# 06_eMMC.net
KiCad netlist of a schematic drawn in Altium Designer
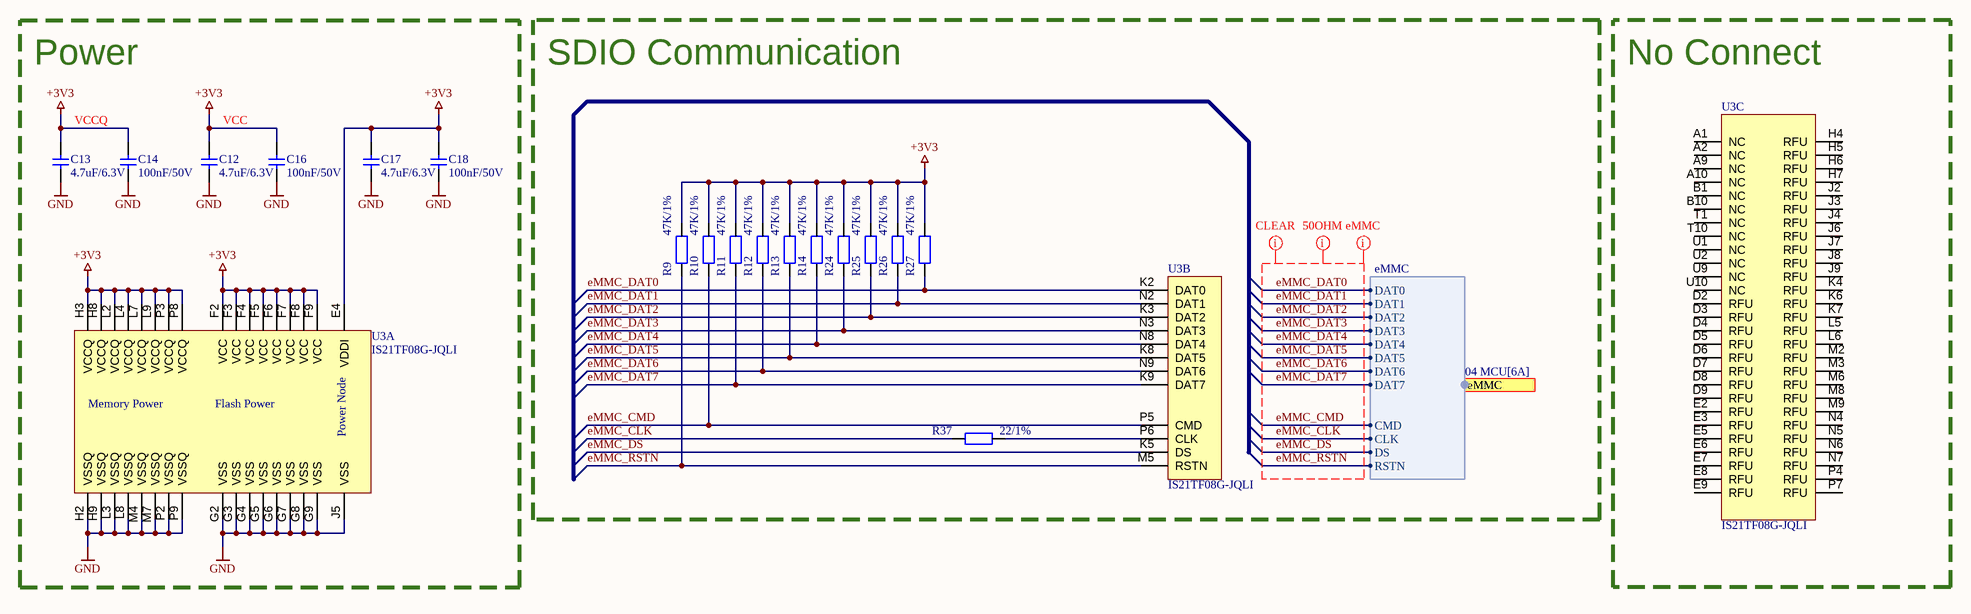
[diagram p0: 06 eMMC.SchDoc]

(export (version "E")
  (design (tool "Eeschema 10.0.6"))
  (components
    (comp (ref "C12")
      (value "4.7uF/6.3V")
      (footprint "CAPC1005X06M-0402")
      (description "4.7 µF ±20% 6.3V Ceramic Capacitor X5R 0402 (1005 Metric)")
      (fields (field (name "MPN") "GRM155R60J475ME47D"))
      (libsource (lib "Symbol") (part "GRM155R60J475ME47D"))
    )
    (comp (ref "C13")
      (value "4.7uF/6.3V")
      (footprint "CAPC1005X06M-0402")
      (description "4.7 µF ±20% 6.3V Ceramic Capacitor X5R 0402 (1005 Metric)")
      (fields (field (name "MPN") "GRM155R60J475ME47D"))
      (libsource (lib "Symbol") (part "GRM155R60J475ME47D"))
    )
    (comp (ref "C14")
      (value "100nF/50V")
      (footprint "CAPC1005X06M-0402")
      (description "0.1 µF ±10% 50V Ceramic Capacitor X7R 0402 (1005 Metric)")
      (fields (field (name "MPN") "GRM155R71H104KE14D"))
      (libsource (lib "Symbol") (part "GRM155R71H104KE14D"))
    )
    (comp (ref "C16")
      (value "100nF/50V")
      (footprint "CAPC1005X06M-0402")
      (description "0.1 µF ±10% 50V Ceramic Capacitor X7R 0402 (1005 Metric)")
      (fields (field (name "MPN") "GRM155R71H104KE14D"))
      (libsource (lib "Symbol") (part "GRM155R71H104KE14D"))
    )
    (comp (ref "C17")
      (value "4.7uF/6.3V")
      (footprint "CAPC1005X06M-0402")
      (description "4.7 µF ±20% 6.3V Ceramic Capacitor X5R 0402 (1005 Metric)")
      (fields (field (name "MPN") "GRM155R60J475ME47D"))
      (libsource (lib "Symbol") (part "GRM155R60J475ME47D"))
    )
    (comp (ref "C18")
      (value "100nF/50V")
      (footprint "CAPC1005X06M-0402")
      (description "0.1 µF ±10% 50V Ceramic Capacitor X7R 0402 (1005 Metric)")
      (fields (field (name "MPN") "GRM155R71H104KE14D"))
      (libsource (lib "Symbol") (part "GRM155R71H104KE14D"))
    )
    (comp (ref "R9")
      (value "47K/1%")
      (footprint "RESC1005X04M-0402")
      (description "47 kOhms ±1% 0.063W, 1/16W Chip Resistor 0402 (1005 Metric) Moisture Resistant Thick Film")
      (fields (field (name "MPN") "RC0402FR-0747KL"))
      (libsource (lib "Symbol") (part "RC0402FR-0747KL"))
    )
    (comp (ref "R10")
      (value "47K/1%")
      (footprint "RESC1005X04M-0402")
      (description "47 kOhms ±1% 0.063W, 1/16W Chip Resistor 0402 (1005 Metric) Moisture Resistant Thick Film")
      (fields (field (name "MPN") "RC0402FR-0747KL"))
      (libsource (lib "Symbol") (part "RC0402FR-0747KL"))
    )
    (comp (ref "R11")
      (value "47K/1%")
      (footprint "RESC1005X04M-0402")
      (description "47 kOhms ±1% 0.063W, 1/16W Chip Resistor 0402 (1005 Metric) Moisture Resistant Thick Film")
      (fields (field (name "MPN") "RC0402FR-0747KL"))
      (libsource (lib "Symbol") (part "RC0402FR-0747KL"))
    )
    (comp (ref "R12")
      (value "47K/1%")
      (footprint "RESC1005X04M-0402")
      (description "47 kOhms ±1% 0.063W, 1/16W Chip Resistor 0402 (1005 Metric) Moisture Resistant Thick Film")
      (fields (field (name "MPN") "RC0402FR-0747KL"))
      (libsource (lib "Symbol") (part "RC0402FR-0747KL"))
    )
    (comp (ref "R13")
      (value "47K/1%")
      (footprint "RESC1005X04M-0402")
      (description "47 kOhms ±1% 0.063W, 1/16W Chip Resistor 0402 (1005 Metric) Moisture Resistant Thick Film")
      (fields (field (name "MPN") "RC0402FR-0747KL"))
      (libsource (lib "Symbol") (part "RC0402FR-0747KL"))
    )
    (comp (ref "R14")
      (value "47K/1%")
      (footprint "RESC1005X04M-0402")
      (description "47 kOhms ±1% 0.063W, 1/16W Chip Resistor 0402 (1005 Metric) Moisture Resistant Thick Film")
      (fields (field (name "MPN") "RC0402FR-0747KL"))
      (libsource (lib "Symbol") (part "RC0402FR-0747KL"))
    )
    (comp (ref "R24")
      (value "47K/1%")
      (footprint "RESC1005X04M-0402")
      (description "47 kOhms ±1% 0.063W, 1/16W Chip Resistor 0402 (1005 Metric) Moisture Resistant Thick Film")
      (fields (field (name "MPN") "RC0402FR-0747KL"))
      (libsource (lib "Symbol") (part "RC0402FR-0747KL"))
    )
    (comp (ref "R25")
      (value "47K/1%")
      (footprint "RESC1005X04M-0402")
      (description "47 kOhms ±1% 0.063W, 1/16W Chip Resistor 0402 (1005 Metric) Moisture Resistant Thick Film")
      (fields (field (name "MPN") "RC0402FR-0747KL"))
      (libsource (lib "Symbol") (part "RC0402FR-0747KL"))
    )
    (comp (ref "R26")
      (value "47K/1%")
      (footprint "RESC1005X04M-0402")
      (description "47 kOhms ±1% 0.063W, 1/16W Chip Resistor 0402 (1005 Metric) Moisture Resistant Thick Film")
      (fields (field (name "MPN") "RC0402FR-0747KL"))
      (libsource (lib "Symbol") (part "RC0402FR-0747KL"))
    )
    (comp (ref "R27")
      (value "47K/1%")
      (footprint "RESC1005X04M-0402")
      (description "47 kOhms ±1% 0.063W, 1/16W Chip Resistor 0402 (1005 Metric) Moisture Resistant Thick Film")
      (fields (field (name "MPN") "RC0402FR-0747KL"))
      (libsource (lib "Symbol") (part "RC0402FR-0747KL"))
    )
    (comp (ref "R37")
      (value "22/1%")
      (footprint "RESC1005X04M-0402")
      (description "22 Ohms ±1% 0.063W, 1/16W Chip Resistor 0402 (1005 Metric) Moisture Resistant Thick Film")
      (fields (field (name "MPN") "RC0402FR-0722RL"))
      (libsource (lib "Symbol") (part "RC0402FR-0722RL"))
    )
    (comp (ref "U3")
      (value "IS21TF08G-JQLI")
      (footprint "BGA180C100P10X18_1400X1400X140")
      (description "FLASH - NAND (TLC) Memory IC 64Gbit MMC 200 MHz 100-LFBGA (14x18)")
      (libsource (lib "Symbol") (part "IS21TF08G-JQLI"))
    )
  )
  (nets
    (net (code "2") (name "+3V3") (class "Default")
      (node (ref "C12") (pin "2") (pinfunction "2_2") (pintype "passive"))
      (node (ref "C13") (pin "2") (pinfunction "2_2") (pintype "passive"))
      (node (ref "C14") (pin "2") (pinfunction "2_2") (pintype "passive"))
      (node (ref "C16") (pin "2") (pinfunction "2_2") (pintype "passive"))
      (node (ref "C17") (pin "2") (pinfunction "2_2") (pintype "passive"))
      (node (ref "C18") (pin "2") (pinfunction "2_2") (pintype "passive"))
      (node (ref "R10") (pin "2") (pinfunction "2_2") (pintype "passive"))
      (node (ref "R11") (pin "2") (pinfunction "2_2") (pintype "passive"))
      (node (ref "R12") (pin "2") (pinfunction "2_2") (pintype "passive"))
      (node (ref "R13") (pin "2") (pinfunction "2_2") (pintype "passive"))
      (node (ref "R14") (pin "2") (pinfunction "2_2") (pintype "passive"))
      (node (ref "R24") (pin "2") (pinfunction "2_2") (pintype "passive"))
      (node (ref "R25") (pin "2") (pinfunction "2_2") (pintype "passive"))
      (node (ref "R26") (pin "2") (pinfunction "2_2") (pintype "passive"))
      (node (ref "R27") (pin "2") (pinfunction "2_2") (pintype "passive"))
      (node (ref "R9") (pin "2") (pinfunction "2_2") (pintype "passive"))
      (node (ref "U3") (pin "E4") (pinfunction "VDDI_E4") (pintype "power_in"))
      (node (ref "U3") (pin "F2") (pinfunction "VCC_F2") (pintype "power_in"))
      (node (ref "U3") (pin "F3") (pinfunction "VCC_F3") (pintype "power_in"))
      (node (ref "U3") (pin "F4") (pinfunction "VCC_F4") (pintype "power_in"))
      (node (ref "U3") (pin "F5") (pinfunction "VCC_F5") (pintype "power_in"))
      (node (ref "U3") (pin "F6") (pinfunction "VCC_F6") (pintype "power_in"))
      (node (ref "U3") (pin "F7") (pinfunction "VCC_F7") (pintype "power_in"))
      (node (ref "U3") (pin "F8") (pinfunction "VCC_F8") (pintype "power_in"))
      (node (ref "U3") (pin "F9") (pinfunction "VCC_F9") (pintype "power_in"))
      (node (ref "U3") (pin "H3") (pinfunction "VCCQ_H3") (pintype "power_in"))
      (node (ref "U3") (pin "H8") (pinfunction "VCCQ_H8") (pintype "power_in"))
      (node (ref "U3") (pin "L2") (pinfunction "VCCQ_L2") (pintype "power_in"))
      (node (ref "U3") (pin "L4") (pinfunction "VCCQ_L4") (pintype "power_in"))
      (node (ref "U3") (pin "L7") (pinfunction "VCCQ_L7") (pintype "power_in"))
      (node (ref "U3") (pin "L9") (pinfunction "VCCQ_L9") (pintype "power_in"))
      (node (ref "U3") (pin "P3") (pinfunction "VCCQ_P3") (pintype "power_in"))
      (node (ref "U3") (pin "P8") (pinfunction "VCCQ_P8") (pintype "power_in"))
    )
    (net (code "3") (name "/eMMC_CLK") (class "Default")
      (node (ref "R37") (pin "1") (pinfunction "1_1") (pintype "passive"))
    )
    (net (code "4") (name "/eMMC_CMD") (class "Default")
      (node (ref "R10") (pin "1") (pinfunction "1_1") (pintype "passive"))
      (node (ref "U3") (pin "P5") (pinfunction "CMD_P5") (pintype "passive"))
    )
    (net (code "5") (name "/eMMC_DAT0") (class "Default")
      (node (ref "R27") (pin "1") (pinfunction "1_1") (pintype "passive"))
      (node (ref "U3") (pin "K2") (pinfunction "DAT0_K2") (pintype "passive"))
    )
    (net (code "6") (name "/eMMC_DAT1") (class "Default")
      (node (ref "R26") (pin "1") (pinfunction "1_1") (pintype "passive"))
      (node (ref "U3") (pin "N2") (pinfunction "DAT1_N2") (pintype "passive"))
    )
    (net (code "7") (name "/eMMC_DAT2") (class "Default")
      (node (ref "R25") (pin "1") (pinfunction "1_1") (pintype "passive"))
      (node (ref "U3") (pin "K3") (pinfunction "DAT2_K3") (pintype "passive"))
    )
    (net (code "8") (name "/eMMC_DAT3") (class "Default")
      (node (ref "R24") (pin "1") (pinfunction "1_1") (pintype "passive"))
      (node (ref "U3") (pin "N3") (pinfunction "DAT3_N3") (pintype "passive"))
    )
    (net (code "9") (name "/eMMC_DAT4") (class "Default")
      (node (ref "R14") (pin "1") (pinfunction "1_1") (pintype "passive"))
      (node (ref "U3") (pin "N8") (pinfunction "DAT4_N8") (pintype "passive"))
    )
    (net (code "10") (name "/eMMC_DAT5") (class "Default")
      (node (ref "R13") (pin "1") (pinfunction "1_1") (pintype "passive"))
      (node (ref "U3") (pin "K8") (pinfunction "DAT5_K8") (pintype "passive"))
    )
    (net (code "11") (name "/eMMC_DAT6") (class "Default")
      (node (ref "R12") (pin "1") (pinfunction "1_1") (pintype "passive"))
      (node (ref "U3") (pin "N9") (pinfunction "DAT6_N9") (pintype "passive"))
    )
    (net (code "12") (name "/eMMC_DAT7") (class "Default")
      (node (ref "R11") (pin "1") (pinfunction "1_1") (pintype "passive"))
      (node (ref "U3") (pin "K9") (pinfunction "DAT7_K9") (pintype "passive"))
    )
    (net (code "13") (name "/eMMC_DS") (class "Default")
      (node (ref "U3") (pin "K5") (pinfunction "DS_K5") (pintype "passive"))
    )
    (net (code "14") (name "/eMMC_RSTN") (class "Default")
      (node (ref "R9") (pin "1") (pinfunction "1_1") (pintype "passive"))
      (node (ref "U3") (pin "M5") (pinfunction "RSTN_M5") (pintype "passive"))
    )
    (net (code "16") (name "GND") (class "Default")
      (node (ref "C12") (pin "1") (pinfunction "1_1") (pintype "passive"))
      (node (ref "C13") (pin "1") (pinfunction "1_1") (pintype "passive"))
      (node (ref "C14") (pin "1") (pinfunction "1_1") (pintype "passive"))
      (node (ref "C16") (pin "1") (pinfunction "1_1") (pintype "passive"))
      (node (ref "C17") (pin "1") (pinfunction "1_1") (pintype "passive"))
      (node (ref "C18") (pin "1") (pinfunction "1_1") (pintype "passive"))
      (node (ref "U3") (pin "G2") (pinfunction "VSS_G2") (pintype "power_in"))
      (node (ref "U3") (pin "G3") (pinfunction "VSS_G3") (pintype "power_in"))
      (node (ref "U3") (pin "G4") (pinfunction "VSS_G4") (pintype "power_in"))
      (node (ref "U3") (pin "G5") (pinfunction "VSS_G5") (pintype "power_in"))
      (node (ref "U3") (pin "G6") (pinfunction "VSS_G6") (pintype "power_in"))
      (node (ref "U3") (pin "G7") (pinfunction "VSS_G7") (pintype "power_in"))
      (node (ref "U3") (pin "G8") (pinfunction "VSS_G8") (pintype "power_in"))
      (node (ref "U3") (pin "G9") (pinfunction "VSS_G9") (pintype "power_in"))
      (node (ref "U3") (pin "H2") (pinfunction "VSSQ_H2") (pintype "power_in"))
      (node (ref "U3") (pin "H9") (pinfunction "VSSQ_H9") (pintype "power_in"))
      (node (ref "U3") (pin "J5") (pinfunction "VSS_J5") (pintype "power_in"))
      (node (ref "U3") (pin "L3") (pinfunction "VSSQ_L3") (pintype "power_in"))
      (node (ref "U3") (pin "L8") (pinfunction "VSSQ_L8") (pintype "power_in"))
      (node (ref "U3") (pin "M4") (pinfunction "VSSQ_M4") (pintype "power_in"))
      (node (ref "U3") (pin "M7") (pinfunction "VSSQ_M7") (pintype "power_in"))
      (node (ref "U3") (pin "P2") (pinfunction "VSSQ_P2") (pintype "power_in"))
      (node (ref "U3") (pin "P9") (pinfunction "VSSQ_P9") (pintype "power_in"))
    )
    (net (code "17") (name "Net-(U3B-CLK)") (class "Default")
      (node (ref "R37") (pin "2") (pinfunction "2_2") (pintype "passive"))
      (node (ref "U3") (pin "P6") (pinfunction "CLK_P6") (pintype "passive"))
    )
    (net (code "18") (name "unconnected-(U3C-NC-PadA1)") (class "Default")
      (node (ref "U3") (pin "A1") (pinfunction "NC_A1") (pintype "passive"))
    )
    (net (code "19") (name "unconnected-(U3C-NC-PadA2)") (class "Default")
      (node (ref "U3") (pin "A2") (pinfunction "NC_A2") (pintype "passive"))
    )
    (net (code "20") (name "unconnected-(U3C-NC-PadA9)") (class "Default")
      (node (ref "U3") (pin "A9") (pinfunction "NC_A9") (pintype "passive"))
    )
    (net (code "21") (name "unconnected-(U3C-NC-PadA10)") (class "Default")
      (node (ref "U3") (pin "A10") (pinfunction "NC_A10") (pintype "passive"))
    )
    (net (code "22") (name "unconnected-(U3C-NC-PadB1)") (class "Default")
      (node (ref "U3") (pin "B1") (pinfunction "NC_B1") (pintype "passive"))
    )
    (net (code "23") (name "unconnected-(U3C-NC-PadB10)") (class "Default")
      (node (ref "U3") (pin "B10") (pinfunction "NC_B10") (pintype "passive"))
    )
    (net (code "24") (name "unconnected-(U3C-NC-PadT1)") (class "Default")
      (node (ref "U3") (pin "T1") (pinfunction "NC_T1") (pintype "passive"))
    )
    (net (code "25") (name "unconnected-(U3C-NC-PadT10)") (class "Default")
      (node (ref "U3") (pin "T10") (pinfunction "NC_T10") (pintype "passive"))
    )
    (net (code "26") (name "unconnected-(U3C-NC-PadU1)") (class "Default")
      (node (ref "U3") (pin "U1") (pinfunction "NC_U1") (pintype "passive"))
    )
    (net (code "27") (name "unconnected-(U3C-NC-PadU2)") (class "Default")
      (node (ref "U3") (pin "U2") (pinfunction "NC_U2") (pintype "passive"))
    )
    (net (code "28") (name "unconnected-(U3C-NC-PadU9)") (class "Default")
      (node (ref "U3") (pin "U9") (pinfunction "NC_U9") (pintype "passive"))
    )
    (net (code "29") (name "unconnected-(U3C-NC-PadU10)") (class "Default")
      (node (ref "U3") (pin "U10") (pinfunction "NC_U10") (pintype "passive"))
    )
    (net (code "30") (name "unconnected-(U3C-RFU-PadD2)") (class "Default")
      (node (ref "U3") (pin "D2") (pinfunction "RFU_D2") (pintype "passive"))
    )
    (net (code "31") (name "unconnected-(U3C-RFU-PadD3)") (class "Default")
      (node (ref "U3") (pin "D3") (pinfunction "RFU_D3") (pintype "passive"))
    )
    (net (code "32") (name "unconnected-(U3C-RFU-PadD4)") (class "Default")
      (node (ref "U3") (pin "D4") (pinfunction "RFU_D4") (pintype "passive"))
    )
    (net (code "33") (name "unconnected-(U3C-RFU-PadD5)") (class "Default")
      (node (ref "U3") (pin "D5") (pinfunction "RFU_D5") (pintype "passive"))
    )
    (net (code "34") (name "unconnected-(U3C-RFU-PadD6)") (class "Default")
      (node (ref "U3") (pin "D6") (pinfunction "RFU_D6") (pintype "passive"))
    )
    (net (code "35") (name "unconnected-(U3C-RFU-PadD7)") (class "Default")
      (node (ref "U3") (pin "D7") (pinfunction "RFU_D7") (pintype "passive"))
    )
    (net (code "36") (name "unconnected-(U3C-RFU-PadD8)") (class "Default")
      (node (ref "U3") (pin "D8") (pinfunction "RFU_D8") (pintype "passive"))
    )
    (net (code "37") (name "unconnected-(U3C-RFU-PadD9)") (class "Default")
      (node (ref "U3") (pin "D9") (pinfunction "RFU_D9") (pintype "passive"))
    )
    (net (code "38") (name "unconnected-(U3C-RFU-PadE2)") (class "Default")
      (node (ref "U3") (pin "E2") (pinfunction "RFU_E2") (pintype "passive"))
    )
    (net (code "39") (name "unconnected-(U3C-RFU-PadE3)") (class "Default")
      (node (ref "U3") (pin "E3") (pinfunction "RFU_E3") (pintype "passive"))
    )
    (net (code "40") (name "unconnected-(U3C-RFU-PadE5)") (class "Default")
      (node (ref "U3") (pin "E5") (pinfunction "RFU_E5") (pintype "passive"))
    )
    (net (code "41") (name "unconnected-(U3C-RFU-PadE6)") (class "Default")
      (node (ref "U3") (pin "E6") (pinfunction "RFU_E6") (pintype "passive"))
    )
    (net (code "42") (name "unconnected-(U3C-RFU-PadE7)") (class "Default")
      (node (ref "U3") (pin "E7") (pinfunction "RFU_E7") (pintype "passive"))
    )
    (net (code "43") (name "unconnected-(U3C-RFU-PadE8)") (class "Default")
      (node (ref "U3") (pin "E8") (pinfunction "RFU_E8") (pintype "passive"))
    )
    (net (code "44") (name "unconnected-(U3C-RFU-PadE9)") (class "Default")
      (node (ref "U3") (pin "E9") (pinfunction "RFU_E9") (pintype "passive"))
    )
    (net (code "45") (name "unconnected-(U3C-RFU-PadH4)") (class "Default")
      (node (ref "U3") (pin "H4") (pinfunction "RFU_H4") (pintype "passive"))
    )
    (net (code "46") (name "unconnected-(U3C-RFU-PadH5)") (class "Default")
      (node (ref "U3") (pin "H5") (pinfunction "RFU_H5") (pintype "passive"))
    )
    (net (code "47") (name "unconnected-(U3C-RFU-PadH6)") (class "Default")
      (node (ref "U3") (pin "H6") (pinfunction "RFU_H6") (pintype "passive"))
    )
    (net (code "48") (name "unconnected-(U3C-RFU-PadH7)") (class "Default")
      (node (ref "U3") (pin "H7") (pinfunction "RFU_H7") (pintype "passive"))
    )
    (net (code "49") (name "unconnected-(U3C-RFU-PadJ2)") (class "Default")
      (node (ref "U3") (pin "J2") (pinfunction "RFU_J2") (pintype "passive"))
    )
    (net (code "50") (name "unconnected-(U3C-RFU-PadJ3)") (class "Default")
      (node (ref "U3") (pin "J3") (pinfunction "RFU_J3") (pintype "passive"))
    )
    (net (code "51") (name "unconnected-(U3C-RFU-PadJ4)") (class "Default")
      (node (ref "U3") (pin "J4") (pinfunction "RFU_J4") (pintype "passive"))
    )
    (net (code "52") (name "unconnected-(U3C-RFU-PadJ6)") (class "Default")
      (node (ref "U3") (pin "J6") (pinfunction "RFU_J6") (pintype "passive"))
    )
    (net (code "53") (name "unconnected-(U3C-RFU-PadJ7)") (class "Default")
      (node (ref "U3") (pin "J7") (pinfunction "RFU_J7") (pintype "passive"))
    )
    (net (code "54") (name "unconnected-(U3C-RFU-PadJ8)") (class "Default")
      (node (ref "U3") (pin "J8") (pinfunction "RFU_J8") (pintype "passive"))
    )
    (net (code "55") (name "unconnected-(U3C-RFU-PadJ9)") (class "Default")
      (node (ref "U3") (pin "J9") (pinfunction "RFU_J9") (pintype "passive"))
    )
    (net (code "56") (name "unconnected-(U3C-RFU-PadK4)") (class "Default")
      (node (ref "U3") (pin "K4") (pinfunction "RFU_K4") (pintype "passive"))
    )
    (net (code "57") (name "unconnected-(U3C-RFU-PadK6)") (class "Default")
      (node (ref "U3") (pin "K6") (pinfunction "RFU_K6") (pintype "passive"))
    )
    (net (code "58") (name "unconnected-(U3C-RFU-PadK7)") (class "Default")
      (node (ref "U3") (pin "K7") (pinfunction "RFU_K7") (pintype "passive"))
    )
    (net (code "59") (name "unconnected-(U3C-RFU-PadL5)") (class "Default")
      (node (ref "U3") (pin "L5") (pinfunction "RFU_L5") (pintype "passive"))
    )
    (net (code "60") (name "unconnected-(U3C-RFU-PadL6)") (class "Default")
      (node (ref "U3") (pin "L6") (pinfunction "RFU_L6") (pintype "passive"))
    )
    (net (code "61") (name "unconnected-(U3C-RFU-PadM2)") (class "Default")
      (node (ref "U3") (pin "M2") (pinfunction "RFU_M2") (pintype "passive"))
    )
    (net (code "62") (name "unconnected-(U3C-RFU-PadM3)") (class "Default")
      (node (ref "U3") (pin "M3") (pinfunction "RFU_M3") (pintype "passive"))
    )
    (net (code "63") (name "unconnected-(U3C-RFU-PadM6)") (class "Default")
      (node (ref "U3") (pin "M6") (pinfunction "RFU_M6") (pintype "passive"))
    )
    (net (code "64") (name "unconnected-(U3C-RFU-PadM8)") (class "Default")
      (node (ref "U3") (pin "M8") (pinfunction "RFU_M8") (pintype "passive"))
    )
    (net (code "65") (name "unconnected-(U3C-RFU-PadM9)") (class "Default")
      (node (ref "U3") (pin "M9") (pinfunction "RFU_M9") (pintype "passive"))
    )
    (net (code "66") (name "unconnected-(U3C-RFU-PadN4)") (class "Default")
      (node (ref "U3") (pin "N4") (pinfunction "RFU_N4") (pintype "passive"))
    )
    (net (code "67") (name "unconnected-(U3C-RFU-PadN5)") (class "Default")
      (node (ref "U3") (pin "N5") (pinfunction "RFU_N5") (pintype "passive"))
    )
    (net (code "68") (name "unconnected-(U3C-RFU-PadN6)") (class "Default")
      (node (ref "U3") (pin "N6") (pinfunction "RFU_N6") (pintype "passive"))
    )
    (net (code "69") (name "unconnected-(U3C-RFU-PadN7)") (class "Default")
      (node (ref "U3") (pin "N7") (pinfunction "RFU_N7") (pintype "passive"))
    )
    (net (code "70") (name "unconnected-(U3C-RFU-PadP4)") (class "Default")
      (node (ref "U3") (pin "P4") (pinfunction "RFU_P4") (pintype "passive"))
    )
    (net (code "71") (name "unconnected-(U3C-RFU-PadP7)") (class "Default")
      (node (ref "U3") (pin "P7") (pinfunction "RFU_P7") (pintype "passive"))
    )
  )
)
